# 1_panel.net
KiCad netlist of a schematic drawn in Altium Designer
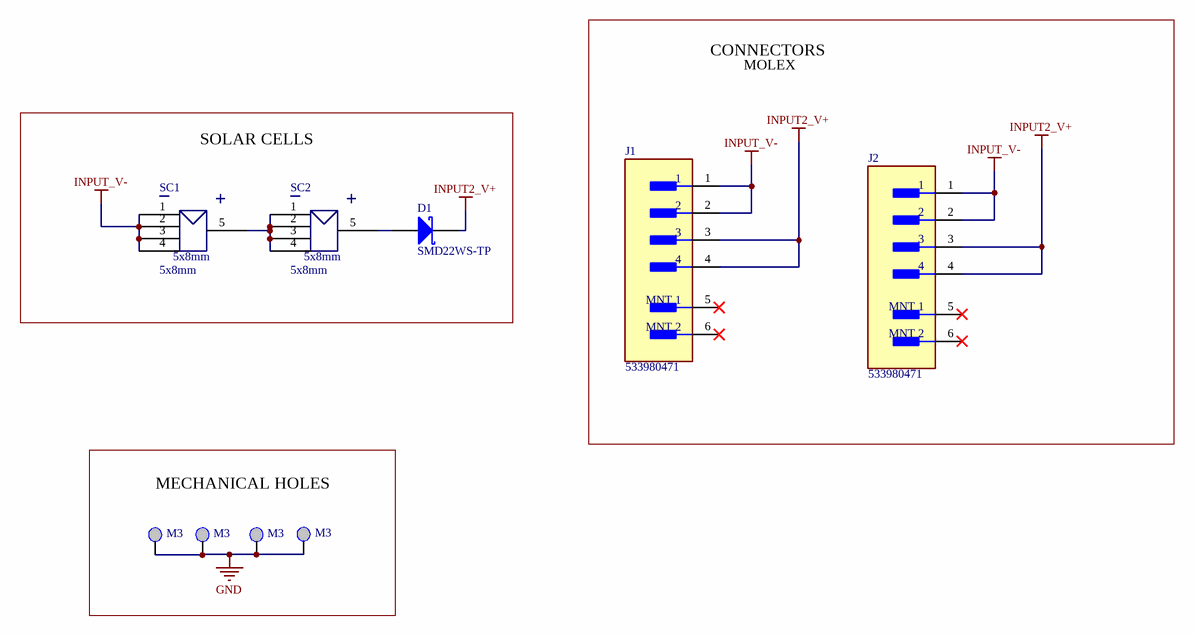
[diagram p0: 1_panel.schdoc]

(export (version "E")
  (design (tool "Eeschema 10.0.6"))
  (components
    (comp (ref "D1")
      (value "SMD22WS-TP")
      (footprint "SOD323F")
      (description "Diode Schottky 20 V 2A Surface Mount SOD-323")
      (libsource (lib "schematics_library_legacy") (part "DIODE_SCHOTTKY_20V_2A_SMD22WS-TP"))
    )
    (comp (ref "J1")
      (value "533980471")
      (footprint "FP-533980471-MFG")
      (description "CONN HEADER SMD 4POS 1.25MM")
      (fields
        (field (name "OCTOPART") "https://octopart.com/53398-0471-molex-655296")
        (field (name "MANUFACTURER") "Molex")
      )
      (libsource (lib "Altium Content Vault") (part "3b6f738a5616415d78381ad43816e4a"))
    )
    (comp (ref "J2")
      (value "533980471")
      (footprint "FP-533980471-MFG")
      (description "CONN HEADER SMD 4POS 1.25MM")
      (fields
        (field (name "OCTOPART") "https://octopart.com/53398-0471-molex-655296")
        (field (name "MANUFACTURER") "Molex")
      )
      (libsource (lib "Altium Content Vault") (part "3b6f738a5616415d78381ad43816e4a"))
    )
    (comp (ref "MEC1")
      (value "M3")
      (footprint "HOLE6x6mm")
      (description "M3 hole")
      (libsource (lib "schematics_library_legacy") (part "M3 hole"))
    )
    (comp (ref "MEC2")
      (value "M3")
      (footprint "HOLE6x6mm")
      (description "M3 hole")
      (libsource (lib "schematics_library_legacy") (part "M3 hole"))
    )
    (comp (ref "MEC3")
      (value "M3")
      (footprint "HOLE6x6mm")
      (description "M3 hole")
      (libsource (lib "schematics_library_legacy") (part "M3 hole"))
    )
    (comp (ref "MEC4")
      (value "M3")
      (footprint "HOLE6x6mm")
      (description "M3 hole")
      (libsource (lib "schematics_library_legacy") (part "M3 hole"))
    )
    (comp (ref "SC1")
      (value "5x8mm")
      (footprint "SOLAR_CELL_TOP_BOT")
      (fields (field (name "MANUFACTURER") "Yim Space"))
      (libsource (lib "Schlib1") (part "SOLAR CELL"))
    )
    (comp (ref "SC2")
      (value "5x8mm")
      (footprint "SOLAR_CELL_TOP_BOT")
      (fields (field (name "MANUFACTURER") "Yim Space"))
      (libsource (lib "Schlib1") (part "SOLAR CELL"))
    )
  )
  (nets
    (net (code "1") (name "GND") (class "Default")
      (node (ref "MEC1") (pin "0") (pinfunction "0_0") (pintype "passive"))
      (node (ref "MEC2") (pin "0") (pinfunction "0_0") (pintype "passive"))
      (node (ref "MEC3") (pin "0") (pinfunction "0_0") (pintype "passive"))
      (node (ref "MEC4") (pin "0") (pinfunction "0_0") (pintype "passive"))
    )
    (net (code "2") (name "INPUT2_V+") (class "Default")
      (node (ref "D1") (pin "1") (pinfunction "K_1") (pintype "passive"))
      (node (ref "J1") (pin "3") (pinfunction "3_3") (pintype "passive"))
      (node (ref "J1") (pin "4") (pinfunction "4_4") (pintype "passive"))
      (node (ref "J2") (pin "3") (pinfunction "3_3") (pintype "passive"))
      (node (ref "J2") (pin "4") (pinfunction "4_4") (pintype "passive"))
    )
    (net (code "3") (name "INPUT_V-") (class "Default")
      (node (ref "J1") (pin "1") (pinfunction "1_1") (pintype "passive"))
      (node (ref "J1") (pin "2") (pinfunction "2_2") (pintype "passive"))
      (node (ref "J2") (pin "1") (pinfunction "1_1") (pintype "passive"))
      (node (ref "J2") (pin "2") (pinfunction "2_2") (pintype "passive"))
      (node (ref "SC1") (pin "1") (pinfunction "V+_1") (pintype "power_in"))
      (node (ref "SC1") (pin "2") (pinfunction "V-_2") (pintype "power_in"))
      (node (ref "SC1") (pin "3") (pinfunction "3_3") (pintype "passive"))
      (node (ref "SC1") (pin "4") (pinfunction "4_4") (pintype "passive"))
    )
    (net (code "4") (name "Net-(D1-A)") (class "Default")
      (node (ref "D1") (pin "2") (pinfunction "A_2") (pintype "passive"))
      (node (ref "SC2") (pin "5") (pinfunction "5_5") (pintype "passive"))
    )
    (net (code "5") (name "Net-(SC2-V+)") (class "Default")
      (node (ref "SC1") (pin "5") (pinfunction "5_5") (pintype "passive"))
      (node (ref "SC2") (pin "1") (pinfunction "V+_1") (pintype "power_in"))
      (node (ref "SC2") (pin "2") (pinfunction "V-_2") (pintype "power_in"))
      (node (ref "SC2") (pin "3") (pinfunction "3_3") (pintype "passive"))
      (node (ref "SC2") (pin "4") (pinfunction "4_4") (pintype "passive"))
    )
    (net (code "6") (name "unconnected-(J1-MNT_1-Pad5)") (class "Default")
      (node (ref "J1") (pin "5") (pinfunction "MNT_1_5") (pintype "passive+no_connect"))
    )
    (net (code "7") (name "unconnected-(J1-MNT_2-Pad6)") (class "Default")
      (node (ref "J1") (pin "6") (pinfunction "MNT_2_6") (pintype "passive+no_connect"))
    )
    (net (code "8") (name "unconnected-(J2-MNT_1-Pad5)") (class "Default")
      (node (ref "J2") (pin "5") (pinfunction "MNT_1_5") (pintype "passive+no_connect"))
    )
    (net (code "9") (name "unconnected-(J2-MNT_2-Pad6)") (class "Default")
      (node (ref "J2") (pin "6") (pinfunction "MNT_2_6") (pintype "passive+no_connect"))
    )
  )
)
